# WiFire.net
KiCad netlist of a schematic drawn in EAGLE
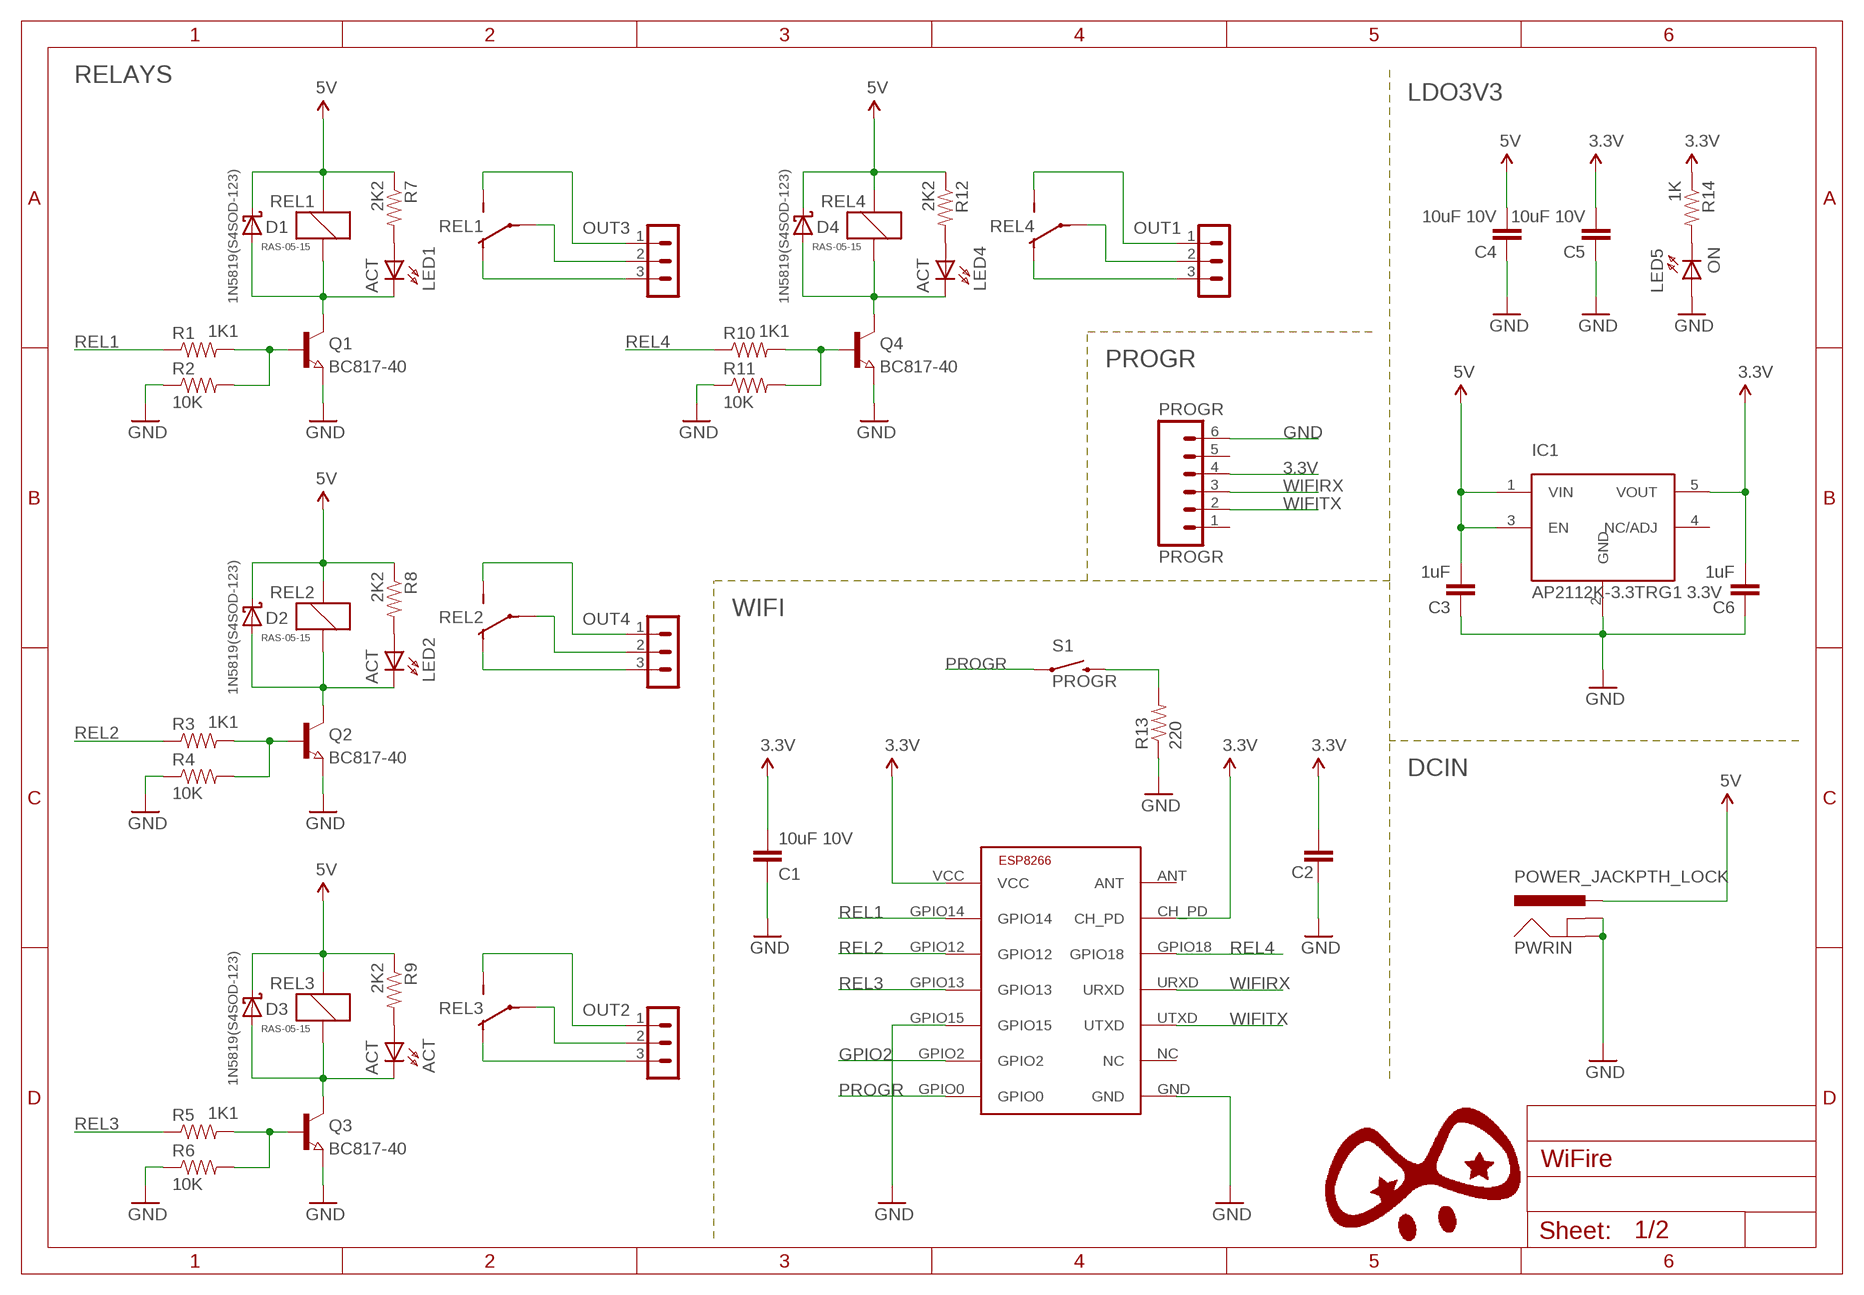
[diagram p0: schematic, sheet 1]
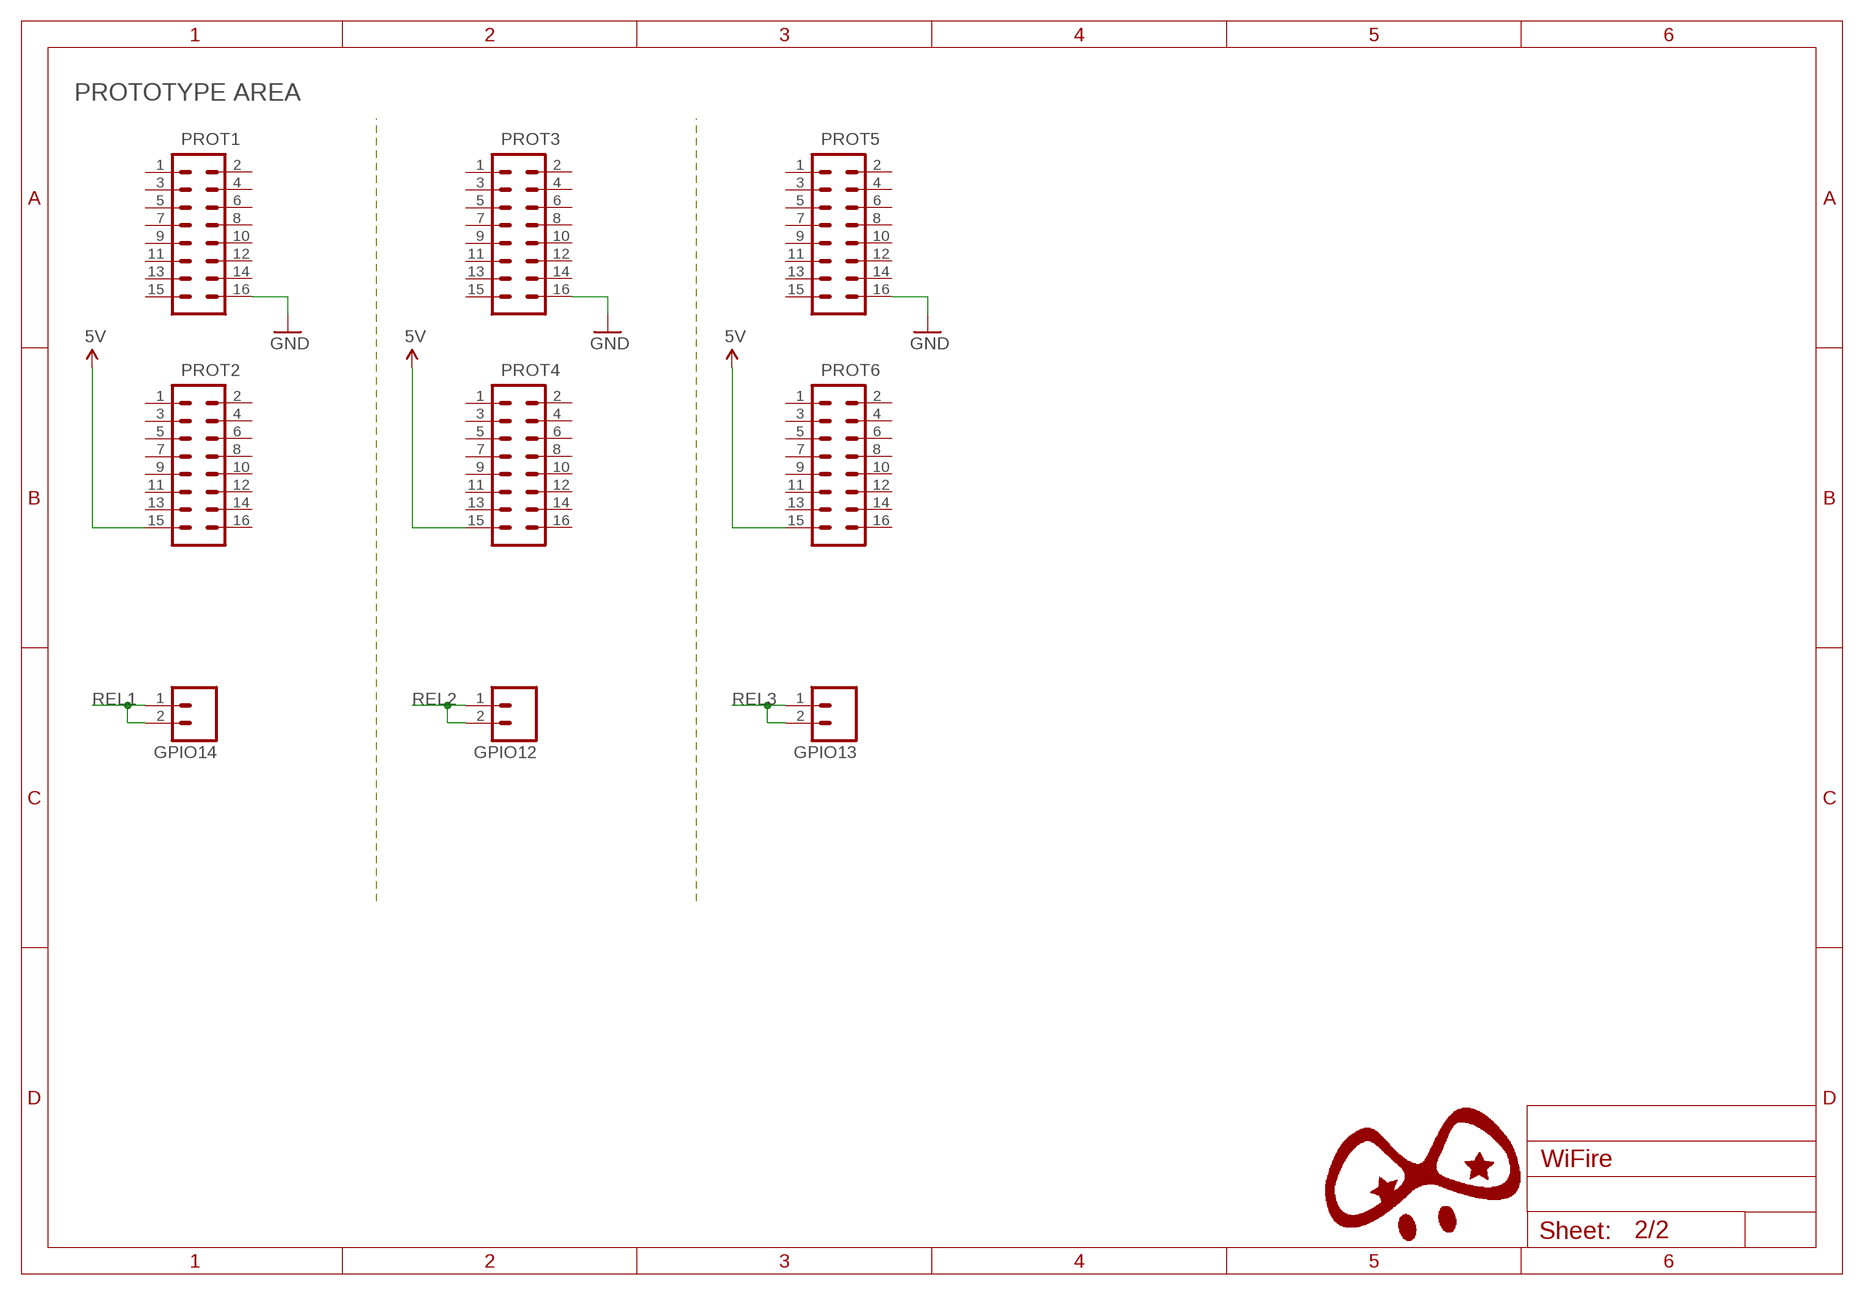
[diagram p1: schematic, sheet 2]

(export (version "E")
  (design (tool "Eeschema 10.0.6"))
  (components
    (comp (ref "ACT")
      (value "ACT")
      (footprint "eagle-import:LED-0603_L")
      (libsource (lib "eagle-import") (part "LED0603DWS_L"))
    )
    (comp (ref "C1")
      (value "10uF 10V")
      (footprint "eagle-import:0402-CAP")
      (libsource (lib "eagle-import") (part "CAP0402-CAP"))
    )
    (comp (ref "C2")
      (value "0.1uF")
      (footprint "eagle-import:0402-CAP")
      (libsource (lib "eagle-import") (part "CAP0402-CAP"))
    )
    (comp (ref "C3")
      (value "1uF")
      (footprint "eagle-import:0402-CAP")
      (libsource (lib "eagle-import") (part "CAP0402-CAP"))
    )
    (comp (ref "C4")
      (value "10uF 10V")
      (footprint "eagle-import:0402-CAP")
      (libsource (lib "eagle-import") (part "CAP0402-CAP"))
    )
    (comp (ref "C5")
      (value "10uF 10V")
      (footprint "eagle-import:0402-CAP")
      (libsource (lib "eagle-import") (part "CAP0402-CAP"))
    )
    (comp (ref "C6")
      (value "1uF")
      (footprint "eagle-import:0402-CAP")
      (libsource (lib "eagle-import") (part "CAP0402-CAP"))
    )
    (comp (ref "D1")
      (value "1N5819(S4SOD-123)")
      (footprint "eagle-import:SOD-123")
      (libsource (lib "eagle-import") (part "SCHOTKKY7.62SS-1N5819(S4SOD-123)"))
    )
    (comp (ref "D2")
      (value "1N5819(S4SOD-123)")
      (footprint "eagle-import:SOD-123")
      (libsource (lib "eagle-import") (part "SCHOTKKY7.62SS-1N5819(S4SOD-123)"))
    )
    (comp (ref "D3")
      (value "1N5819(S4SOD-123)")
      (footprint "eagle-import:SOD-123")
      (libsource (lib "eagle-import") (part "SCHOTKKY7.62SS-1N5819(S4SOD-123)"))
    )
    (comp (ref "D4")
      (value "1N5819(S4SOD-123)")
      (footprint "eagle-import:SOD-123")
      (libsource (lib "eagle-import") (part "SCHOTKKY7.62SS-1N5819(S4SOD-123)"))
    )
    (comp (ref "IC1")
      (value "AP2112K-3.3TRG1 3.3V")
      (footprint "eagle-import:SOT23-5")
      (libsource (lib "eagle-import") (part "5PIN_REG"))
    )
    (comp (ref "LED1")
      (value "ACT")
      (footprint "eagle-import:LED-0603_L")
      (libsource (lib "eagle-import") (part "LED0603DWS_L"))
    )
    (comp (ref "LED2")
      (value "ACT")
      (footprint "eagle-import:LED-0603_L")
      (libsource (lib "eagle-import") (part "LED0603DWS_L"))
    )
    (comp (ref "LED4")
      (value "ACT")
      (footprint "eagle-import:LED-0603_L")
      (libsource (lib "eagle-import") (part "LED0603DWS_L"))
    )
    (comp (ref "LED5")
      (value "ON")
      (footprint "eagle-import:LED-0603_L")
      (libsource (lib "eagle-import") (part "LED0603DWS_L"))
    )
    (comp (ref "OUT1")
      (value "CON3-DG306-5.0_3P(TB3-5MM)")
      (footprint "eagle-import:DG306-5.0_3P")
      (libsource (lib "eagle-import") (part "CON3-DG306-5.0_3P(TB3-5MM)"))
    )
    (comp (ref "OUT2")
      (value "CON3-DG306-5.0_3P(TB3-5MM)")
      (footprint "eagle-import:DG306-5.0_3P")
      (libsource (lib "eagle-import") (part "CON3-DG306-5.0_3P(TB3-5MM)"))
    )
    (comp (ref "OUT3")
      (value "CON3-DG306-5.0_3P(TB3-5MM)")
      (footprint "eagle-import:DG306-5.0_3P")
      (libsource (lib "eagle-import") (part "CON3-DG306-5.0_3P(TB3-5MM)"))
    )
    (comp (ref "OUT4")
      (value "CON3-DG306-5.0_3P(TB3-5MM)")
      (footprint "eagle-import:DG306-5.0_3P")
      (libsource (lib "eagle-import") (part "CON3-DG306-5.0_3P(TB3-5MM)"))
    )
    (comp (ref "PROGR")
      (value "PROGR")
      (footprint "eagle-import:1X06_SMD_MALE")
      (libsource (lib "eagle-import") (part "M06SMD_MALE"))
    )
    (comp (ref "PWRIN")
      (value "POWER_JACKPTH_LOCK")
      (footprint "eagle-import:POWER_JACK_PTH_LOCK")
      (libsource (lib "eagle-import") (part "POWER_JACKPTH_LOCK"))
    )
    (comp (ref "Q1")
      (value "BC817-40")
      (footprint "eagle-import:SOT23")
      (libsource (lib "eagle-import") (part "NPN-TRANSISTOR_SOT23"))
    )
    (comp (ref "Q2")
      (value "BC817-40")
      (footprint "eagle-import:SOT23")
      (libsource (lib "eagle-import") (part "NPN-TRANSISTOR_SOT23"))
    )
    (comp (ref "Q3")
      (value "BC817-40")
      (footprint "eagle-import:SOT23")
      (libsource (lib "eagle-import") (part "NPN-TRANSISTOR_SOT23"))
    )
    (comp (ref "Q4")
      (value "BC817-40")
      (footprint "eagle-import:SOT23")
      (libsource (lib "eagle-import") (part "NPN-TRANSISTOR_SOT23"))
    )
    (comp (ref "R1")
      (value "1K1")
      (footprint "eagle-import:0402-RES")
      (libsource (lib "eagle-import") (part "RESISTOR0402-RES"))
    )
    (comp (ref "R2")
      (value "10K")
      (footprint "eagle-import:0402-RES")
      (libsource (lib "eagle-import") (part "RESISTOR0402-RES"))
    )
    (comp (ref "R3")
      (value "1K1")
      (footprint "eagle-import:0402-RES")
      (libsource (lib "eagle-import") (part "RESISTOR0402-RES"))
    )
    (comp (ref "R4")
      (value "10K")
      (footprint "eagle-import:0402-RES")
      (libsource (lib "eagle-import") (part "RESISTOR0402-RES"))
    )
    (comp (ref "R5")
      (value "1K1")
      (footprint "eagle-import:0402-RES")
      (libsource (lib "eagle-import") (part "RESISTOR0402-RES"))
    )
    (comp (ref "R6")
      (value "10K")
      (footprint "eagle-import:0402-RES")
      (libsource (lib "eagle-import") (part "RESISTOR0402-RES"))
    )
    (comp (ref "R7")
      (value "2K2")
      (footprint "eagle-import:0402-RES")
      (libsource (lib "eagle-import") (part "RESISTOR0402-RES"))
    )
    (comp (ref "R8")
      (value "2K2")
      (footprint "eagle-import:0402-RES")
      (libsource (lib "eagle-import") (part "RESISTOR0402-RES"))
    )
    (comp (ref "R9")
      (value "2K2")
      (footprint "eagle-import:0402-RES")
      (libsource (lib "eagle-import") (part "RESISTOR0402-RES"))
    )
    (comp (ref "R10")
      (value "1K1")
      (footprint "eagle-import:0402-RES")
      (libsource (lib "eagle-import") (part "RESISTOR0402-RES"))
    )
    (comp (ref "R11")
      (value "10K")
      (footprint "eagle-import:0402-RES")
      (libsource (lib "eagle-import") (part "RESISTOR0402-RES"))
    )
    (comp (ref "R12")
      (value "2K2")
      (footprint "eagle-import:0402-RES")
      (libsource (lib "eagle-import") (part "RESISTOR0402-RES"))
    )
    (comp (ref "R13")
      (value "220")
      (footprint "eagle-import:0402-RES")
      (libsource (lib "eagle-import") (part "RESISTOR0402-RES"))
    )
    (comp (ref "R14")
      (value "1K")
      (footprint "eagle-import:0402-RES")
      (libsource (lib "eagle-import") (part "RESISTOR0402-RES"))
    )
    (comp (ref "REL1")
      (value "RAS-05-15")
      (footprint "eagle-import:H200-FAT")
      (libsource (lib "eagle-import") (part "RELAYH200F"))
    )
    (comp (ref "REL2")
      (value "RAS-05-15")
      (footprint "eagle-import:H200-FAT")
      (libsource (lib "eagle-import") (part "RELAYH200F"))
    )
    (comp (ref "REL3")
      (value "RAS-05-15")
      (footprint "eagle-import:H200-FAT")
      (libsource (lib "eagle-import") (part "RELAYH200F"))
    )
    (comp (ref "REL4")
      (value "RAS-05-15")
      (footprint "eagle-import:H200-FAT")
      (libsource (lib "eagle-import") (part "RELAYH200F"))
    )
    (comp (ref "S1")
      (value "PROGR")
      (footprint "eagle-import:TACTILE-PTH-SIDEEZ")
      (libsource (lib "eagle-import") (part "SWITCH-MOMENTARY-2SIDE_EZ"))
    )
    (comp (ref "U1")
      (value "ESP8266")
      (footprint "eagle-import:ESP-03")
      (libsource (lib "eagle-import") (part "ESP8266"))
    )
    (comp (ref "GPIO12")
      (value "M02PTH")
      (footprint "eagle-import:1X02")
      (libsource (lib "eagle-import") (part "M02PTH"))
    )
    (comp (ref "GPIO13")
      (value "M02PTH")
      (footprint "eagle-import:1X02")
      (libsource (lib "eagle-import") (part "M02PTH"))
    )
    (comp (ref "GPIO14")
      (value "M02PTH")
      (footprint "eagle-import:1X02")
      (libsource (lib "eagle-import") (part "M02PTH"))
    )
    (comp (ref "PROT1")
      (value "M08X2")
      (footprint "eagle-import:2X8")
      (libsource (lib "eagle-import") (part "M08X2"))
    )
    (comp (ref "PROT2")
      (value "M08X2")
      (footprint "eagle-import:2X8")
      (libsource (lib "eagle-import") (part "M08X2"))
    )
    (comp (ref "PROT3")
      (value "M08X2")
      (footprint "eagle-import:2X8")
      (libsource (lib "eagle-import") (part "M08X2"))
    )
    (comp (ref "PROT4")
      (value "M08X2")
      (footprint "eagle-import:2X8")
      (libsource (lib "eagle-import") (part "M08X2"))
    )
    (comp (ref "PROT5")
      (value "M08X2")
      (footprint "eagle-import:2X8")
      (libsource (lib "eagle-import") (part "M08X2"))
    )
    (comp (ref "PROT6")
      (value "M08X2")
      (footprint "eagle-import:2X8")
      (libsource (lib "eagle-import") (part "M08X2"))
    )
  )
  (nets
    (net (code "1") (name "3.3V") (class "Default")
      (node (ref "C1") (pin "2") (pinfunction "2_2") (pintype "passive"))
      (node (ref "C2") (pin "2") (pinfunction "2_2") (pintype "passive"))
      (node (ref "C5") (pin "2") (pinfunction "2_2") (pintype "passive"))
      (node (ref "C6") (pin "2") (pinfunction "2_2") (pintype "passive"))
      (node (ref "IC1") (pin "5") (pinfunction "VOUT_5") (pintype "bidirectional"))
      (node (ref "PROGR") (pin "4") (pinfunction "4_4") (pintype "passive"))
      (node (ref "R14") (pin "1") (pinfunction "1_1") (pintype "passive"))
      (node (ref "U1") (pin "CH_PD") (pinfunction "CH_PD_CH_PD") (pintype "bidirectional"))
      (node (ref "U1") (pin "VCC") (pinfunction "VCC_VCC") (pintype "bidirectional"))
    )
    (net (code "2") (name "5V") (class "Default")
      (node (ref "C3") (pin "2") (pinfunction "2_2") (pintype "passive"))
      (node (ref "C4") (pin "2") (pinfunction "2_2") (pintype "passive"))
      (node (ref "D1") (pin "C") (pinfunction "C_C") (pintype "passive"))
      (node (ref "D2") (pin "C") (pinfunction "C_C") (pintype "passive"))
      (node (ref "D3") (pin "C") (pinfunction "C_C") (pintype "passive"))
      (node (ref "D4") (pin "C") (pinfunction "C_C") (pintype "passive"))
      (node (ref "IC1") (pin "1") (pinfunction "VIN_1") (pintype "bidirectional"))
      (node (ref "IC1") (pin "3") (pinfunction "EN_3") (pintype "bidirectional"))
      (node (ref "PROT2") (pin "15") (pinfunction "15_15") (pintype "passive"))
      (node (ref "PROT4") (pin "15") (pinfunction "15_15") (pintype "passive"))
      (node (ref "PROT6") (pin "15") (pinfunction "15_15") (pintype "passive"))
      (node (ref "PWRIN") (pin "PWR") (pinfunction "PWR_PWR") (pintype "bidirectional"))
      (node (ref "R12") (pin "1") (pinfunction "1_1") (pintype "passive"))
      (node (ref "R7") (pin "1") (pinfunction "1_1") (pintype "passive"))
      (node (ref "R8") (pin "1") (pinfunction "1_1") (pintype "passive"))
      (node (ref "R9") (pin "1") (pinfunction "1_1") (pintype "passive"))
      (node (ref "REL1") (pin "1") (pinfunction "1_1") (pintype "passive"))
      (node (ref "REL2") (pin "1") (pinfunction "1_1") (pintype "passive"))
      (node (ref "REL3") (pin "1") (pinfunction "1_1") (pintype "passive"))
      (node (ref "REL4") (pin "1") (pinfunction "1_1") (pintype "passive"))
    )
    (net (code "3") (name "GND") (class "Default")
      (node (ref "C1") (pin "1") (pinfunction "1_1") (pintype "passive"))
      (node (ref "C2") (pin "1") (pinfunction "1_1") (pintype "passive"))
      (node (ref "C3") (pin "1") (pinfunction "1_1") (pintype "passive"))
      (node (ref "C4") (pin "1") (pinfunction "1_1") (pintype "passive"))
      (node (ref "C5") (pin "1") (pinfunction "1_1") (pintype "passive"))
      (node (ref "C6") (pin "1") (pinfunction "1_1") (pintype "passive"))
      (node (ref "IC1") (pin "2") (pinfunction "GND_2") (pintype "bidirectional"))
      (node (ref "LED5") (pin "A") (pinfunction "A_A") (pintype "passive"))
      (node (ref "PROGR") (pin "6") (pinfunction "6_6") (pintype "passive"))
      (node (ref "PROT1") (pin "16") (pinfunction "16_16") (pintype "passive"))
      (node (ref "PROT3") (pin "16") (pinfunction "16_16") (pintype "passive"))
      (node (ref "PROT5") (pin "16") (pinfunction "16_16") (pintype "passive"))
      (node (ref "PWRIN") (pin "GND") (pinfunction "GND_GND") (pintype "bidirectional"))
      (node (ref "PWRIN") (pin "GNDBREAK") (pinfunction "GNDBREAK_GNDBREAK") (pintype "bidirectional"))
      (node (ref "Q1") (pin "2") (pinfunction "E_2") (pintype "passive"))
      (node (ref "Q2") (pin "2") (pinfunction "E_2") (pintype "passive"))
      (node (ref "Q3") (pin "2") (pinfunction "E_2") (pintype "passive"))
      (node (ref "Q4") (pin "2") (pinfunction "E_2") (pintype "passive"))
      (node (ref "R11") (pin "1") (pinfunction "1_1") (pintype "passive"))
      (node (ref "R13") (pin "1") (pinfunction "1_1") (pintype "passive"))
      (node (ref "R2") (pin "1") (pinfunction "1_1") (pintype "passive"))
      (node (ref "R4") (pin "1") (pinfunction "1_1") (pintype "passive"))
      (node (ref "R6") (pin "1") (pinfunction "1_1") (pintype "passive"))
      (node (ref "U1") (pin "GND") (pinfunction "GND_GND") (pintype "bidirectional"))
      (node (ref "U1") (pin "GPIO15") (pinfunction "GPIO15_GPIO15") (pintype "bidirectional"))
    )
    (net (code "4") (name "GPIO2") (class "Default")
      (node (ref "U1") (pin "GPIO2") (pinfunction "GPIO2_GPIO2") (pintype "bidirectional"))
    )
    (net (code "5") (name "Net-(ACT-PadA)") (class "Default")
      (node (ref "ACT") (pin "A") (pinfunction "A_A") (pintype "passive"))
      (node (ref "R9") (pin "2") (pinfunction "2_2") (pintype "passive"))
    )
    (net (code "6") (name "Net-(LED1-PadA)") (class "Default")
      (node (ref "LED1") (pin "A") (pinfunction "A_A") (pintype "passive"))
      (node (ref "R7") (pin "2") (pinfunction "2_2") (pintype "passive"))
    )
    (net (code "7") (name "Net-(LED2-PadA)") (class "Default")
      (node (ref "LED2") (pin "A") (pinfunction "A_A") (pintype "passive"))
      (node (ref "R8") (pin "2") (pinfunction "2_2") (pintype "passive"))
    )
    (net (code "8") (name "Net-(LED4-PadA)") (class "Default")
      (node (ref "LED4") (pin "A") (pinfunction "A_A") (pintype "passive"))
      (node (ref "R12") (pin "2") (pinfunction "2_2") (pintype "passive"))
    )
    (net (code "9") (name "Net-(LED5-PadC)") (class "Default")
      (node (ref "LED5") (pin "C") (pinfunction "C_C") (pintype "passive"))
      (node (ref "R14") (pin "2") (pinfunction "2_2") (pintype "passive"))
    )
    (net (code "10") (name "Net-(OUT1-Pad1)") (class "Default")
      (node (ref "OUT1") (pin "1") (pinfunction "1_1") (pintype "passive"))
      (node (ref "REL4") (pin "S") (pinfunction "S_S") (pintype "passive"))
    )
    (net (code "11") (name "Net-(OUT1-Pad2)") (class "Default")
      (node (ref "OUT1") (pin "2") (pinfunction "2_2") (pintype "passive"))
      (node (ref "REL4") (pin "P") (pinfunction "P_P") (pintype "passive"))
    )
    (net (code "12") (name "Net-(OUT1-Pad3)") (class "Default")
      (node (ref "OUT1") (pin "3") (pinfunction "3_3") (pintype "passive"))
      (node (ref "REL4") (pin "O") (pinfunction "O_O") (pintype "passive"))
    )
    (net (code "13") (name "Net-(OUT2-Pad1)") (class "Default")
      (node (ref "OUT2") (pin "1") (pinfunction "1_1") (pintype "passive"))
      (node (ref "REL3") (pin "S") (pinfunction "S_S") (pintype "passive"))
    )
    (net (code "14") (name "Net-(OUT2-Pad2)") (class "Default")
      (node (ref "OUT2") (pin "2") (pinfunction "2_2") (pintype "passive"))
      (node (ref "REL3") (pin "P") (pinfunction "P_P") (pintype "passive"))
    )
    (net (code "15") (name "Net-(OUT2-Pad3)") (class "Default")
      (node (ref "OUT2") (pin "3") (pinfunction "3_3") (pintype "passive"))
      (node (ref "REL3") (pin "O") (pinfunction "O_O") (pintype "passive"))
    )
    (net (code "16") (name "Net-(OUT3-Pad1)") (class "Default")
      (node (ref "OUT3") (pin "1") (pinfunction "1_1") (pintype "passive"))
      (node (ref "REL1") (pin "S") (pinfunction "S_S") (pintype "passive"))
    )
    (net (code "17") (name "Net-(OUT3-Pad2)") (class "Default")
      (node (ref "OUT3") (pin "2") (pinfunction "2_2") (pintype "passive"))
      (node (ref "REL1") (pin "P") (pinfunction "P_P") (pintype "passive"))
    )
    (net (code "18") (name "Net-(OUT3-Pad3)") (class "Default")
      (node (ref "OUT3") (pin "3") (pinfunction "3_3") (pintype "passive"))
      (node (ref "REL1") (pin "O") (pinfunction "O_O") (pintype "passive"))
    )
    (net (code "19") (name "Net-(OUT4-Pad1)") (class "Default")
      (node (ref "OUT4") (pin "1") (pinfunction "1_1") (pintype "passive"))
      (node (ref "REL2") (pin "S") (pinfunction "S_S") (pintype "passive"))
    )
    (net (code "20") (name "Net-(OUT4-Pad2)") (class "Default")
      (node (ref "OUT4") (pin "2") (pinfunction "2_2") (pintype "passive"))
      (node (ref "REL2") (pin "P") (pinfunction "P_P") (pintype "passive"))
    )
    (net (code "21") (name "Net-(OUT4-Pad3)") (class "Default")
      (node (ref "OUT4") (pin "3") (pinfunction "3_3") (pintype "passive"))
      (node (ref "REL2") (pin "O") (pinfunction "O_O") (pintype "passive"))
    )
    (net (code "22") (name "Net-(Q1-B)") (class "Default")
      (node (ref "Q1") (pin "1") (pinfunction "B_1") (pintype "passive"))
      (node (ref "R1") (pin "2") (pinfunction "2_2") (pintype "passive"))
      (node (ref "R2") (pin "2") (pinfunction "2_2") (pintype "passive"))
    )
    (net (code "23") (name "Net-(Q1-C)") (class "Default")
      (node (ref "D1") (pin "A") (pinfunction "A_A") (pintype "passive"))
      (node (ref "LED1") (pin "C") (pinfunction "C_C") (pintype "passive"))
      (node (ref "Q1") (pin "3") (pinfunction "C_3") (pintype "passive"))
      (node (ref "REL1") (pin "2") (pinfunction "2_2") (pintype "passive"))
    )
    (net (code "24") (name "Net-(Q2-B)") (class "Default")
      (node (ref "Q2") (pin "1") (pinfunction "B_1") (pintype "passive"))
      (node (ref "R3") (pin "2") (pinfunction "2_2") (pintype "passive"))
      (node (ref "R4") (pin "2") (pinfunction "2_2") (pintype "passive"))
    )
    (net (code "25") (name "Net-(Q2-C)") (class "Default")
      (node (ref "D2") (pin "A") (pinfunction "A_A") (pintype "passive"))
      (node (ref "LED2") (pin "C") (pinfunction "C_C") (pintype "passive"))
      (node (ref "Q2") (pin "3") (pinfunction "C_3") (pintype "passive"))
      (node (ref "REL2") (pin "2") (pinfunction "2_2") (pintype "passive"))
    )
    (net (code "26") (name "Net-(Q3-B)") (class "Default")
      (node (ref "Q3") (pin "1") (pinfunction "B_1") (pintype "passive"))
      (node (ref "R5") (pin "2") (pinfunction "2_2") (pintype "passive"))
      (node (ref "R6") (pin "2") (pinfunction "2_2") (pintype "passive"))
    )
    (net (code "27") (name "Net-(Q3-C)") (class "Default")
      (node (ref "ACT") (pin "C") (pinfunction "C_C") (pintype "passive"))
      (node (ref "D3") (pin "A") (pinfunction "A_A") (pintype "passive"))
      (node (ref "Q3") (pin "3") (pinfunction "C_3") (pintype "passive"))
      (node (ref "REL3") (pin "2") (pinfunction "2_2") (pintype "passive"))
    )
    (net (code "28") (name "Net-(Q4-B)") (class "Default")
      (node (ref "Q4") (pin "1") (pinfunction "B_1") (pintype "passive"))
      (node (ref "R10") (pin "2") (pinfunction "2_2") (pintype "passive"))
      (node (ref "R11") (pin "2") (pinfunction "2_2") (pintype "passive"))
    )
    (net (code "29") (name "Net-(Q4-C)") (class "Default")
      (node (ref "D4") (pin "A") (pinfunction "A_A") (pintype "passive"))
      (node (ref "LED4") (pin "C") (pinfunction "C_C") (pintype "passive"))
      (node (ref "Q4") (pin "3") (pinfunction "C_3") (pintype "passive"))
      (node (ref "REL4") (pin "2") (pinfunction "2_2") (pintype "passive"))
    )
    (net (code "30") (name "Net-(R13-Pad2)") (class "Default")
      (node (ref "R13") (pin "2") (pinfunction "2_2") (pintype "passive"))
      (node (ref "S1") (pin "2") (pinfunction "2_2") (pintype "passive"))
    )
    (net (code "31") (name "PROGR") (class "Default")
      (node (ref "S1") (pin "1") (pinfunction "1_1") (pintype "passive"))
      (node (ref "U1") (pin "GPIO0") (pinfunction "GPIO0_GPIO0") (pintype "bidirectional"))
    )
    (net (code "32") (name "REL1") (class "Default")
      (node (ref "GPIO14") (pin "1") (pinfunction "1_1") (pintype "passive"))
      (node (ref "GPIO14") (pin "2") (pinfunction "2_2") (pintype "passive"))
      (node (ref "R1") (pin "1") (pinfunction "1_1") (pintype "passive"))
      (node (ref "U1") (pin "GPIO14") (pinfunction "GPIO14_GPIO14") (pintype "bidirectional"))
    )
    (net (code "33") (name "REL2") (class "Default")
      (node (ref "GPIO12") (pin "1") (pinfunction "1_1") (pintype "passive"))
      (node (ref "GPIO12") (pin "2") (pinfunction "2_2") (pintype "passive"))
      (node (ref "R3") (pin "1") (pinfunction "1_1") (pintype "passive"))
      (node (ref "U1") (pin "GPIO12") (pinfunction "GPIO12_GPIO12") (pintype "bidirectional"))
    )
    (net (code "34") (name "REL3") (class "Default")
      (node (ref "GPIO13") (pin "1") (pinfunction "1_1") (pintype "passive"))
      (node (ref "GPIO13") (pin "2") (pinfunction "2_2") (pintype "passive"))
      (node (ref "R5") (pin "1") (pinfunction "1_1") (pintype "passive"))
      (node (ref "U1") (pin "GPIO13") (pinfunction "GPIO13_GPIO13") (pintype "bidirectional"))
    )
    (net (code "35") (name "REL4") (class "Default")
      (node (ref "R10") (pin "1") (pinfunction "1_1") (pintype "passive"))
      (node (ref "U1") (pin "GPIO18") (pinfunction "GPIO18_GPIO18") (pintype "bidirectional"))
    )
    (net (code "36") (name "WIFIRX") (class "Default")
      (node (ref "PROGR") (pin "3") (pinfunction "3_3") (pintype "passive"))
      (node (ref "U1") (pin "URXD") (pinfunction "URXD_URXD") (pintype "bidirectional"))
    )
    (net (code "37") (name "WIFITX") (class "Default")
      (node (ref "PROGR") (pin "2") (pinfunction "2_2") (pintype "passive"))
      (node (ref "U1") (pin "UTXD") (pinfunction "UTXD_UTXD") (pintype "bidirectional"))
    )
    (net (code "38") (name "unconnected-(IC1-NC{slash}ADJ-Pad4)") (class "Default")
      (node (ref "IC1") (pin "4") (pinfunction "NC/ADJ_4") (pintype "bidirectional"))
    )
    (net (code "39") (name "unconnected-(PROGR-Pad1)") (class "Default")
      (node (ref "PROGR") (pin "1") (pinfunction "1_1") (pintype "passive"))
    )
    (net (code "40") (name "unconnected-(PROGR-Pad5)") (class "Default")
      (node (ref "PROGR") (pin "5") (pinfunction "5_5") (pintype "passive"))
    )
    (net (code "41") (name "unconnected-(PROT1-Pad1)") (class "Default")
      (node (ref "PROT1") (pin "1") (pinfunction "1_1") (pintype "passive"))
    )
    (net (code "42") (name "unconnected-(PROT1-Pad2)") (class "Default")
      (node (ref "PROT1") (pin "2") (pinfunction "2_2") (pintype "passive"))
    )
    (net (code "43") (name "unconnected-(PROT1-Pad3)") (class "Default")
      (node (ref "PROT1") (pin "3") (pinfunction "3_3") (pintype "passive"))
    )
    (net (code "44") (name "unconnected-(PROT1-Pad4)") (class "Default")
      (node (ref "PROT1") (pin "4") (pinfunction "4_4") (pintype "passive"))
    )
    (net (code "45") (name "unconnected-(PROT1-Pad5)") (class "Default")
      (node (ref "PROT1") (pin "5") (pinfunction "5_5") (pintype "passive"))
    )
    (net (code "46") (name "unconnected-(PROT1-Pad6)") (class "Default")
      (node (ref "PROT1") (pin "6") (pinfunction "6_6") (pintype "passive"))
    )
    (net (code "47") (name "unconnected-(PROT1-Pad7)") (class "Default")
      (node (ref "PROT1") (pin "7") (pinfunction "7_7") (pintype "passive"))
    )
    (net (code "48") (name "unconnected-(PROT1-Pad8)") (class "Default")
      (node (ref "PROT1") (pin "8") (pinfunction "8_8") (pintype "passive"))
    )
    (net (code "49") (name "unconnected-(PROT1-Pad9)") (class "Default")
      (node (ref "PROT1") (pin "9") (pinfunction "9_9") (pintype "passive"))
    )
    (net (code "50") (name "unconnected-(PROT1-Pad10)") (class "Default")
      (node (ref "PROT1") (pin "10") (pinfunction "10_10") (pintype "passive"))
    )
    (net (code "51") (name "unconnected-(PROT1-Pad11)") (class "Default")
      (node (ref "PROT1") (pin "11") (pinfunction "11_11") (pintype "passive"))
    )
    (net (code "52") (name "unconnected-(PROT1-Pad12)") (class "Default")
      (node (ref "PROT1") (pin "12") (pinfunction "12_12") (pintype "passive"))
    )
    (net (code "53") (name "unconnected-(PROT1-Pad13)") (class "Default")
      (node (ref "PROT1") (pin "13") (pinfunction "13_13") (pintype "passive"))
    )
    (net (code "54") (name "unconnected-(PROT1-Pad14)") (class "Default")
      (node (ref "PROT1") (pin "14") (pinfunction "14_14") (pintype "passive"))
    )
    (net (code "55") (name "unconnected-(PROT1-Pad15)") (class "Default")
      (node (ref "PROT1") (pin "15") (pinfunction "15_15") (pintype "passive"))
    )
    (net (code "56") (name "unconnected-(PROT2-Pad1)") (class "Default")
      (node (ref "PROT2") (pin "1") (pinfunction "1_1") (pintype "passive"))
    )
    (net (code "57") (name "unconnected-(PROT2-Pad2)") (class "Default")
      (node (ref "PROT2") (pin "2") (pinfunction "2_2") (pintype "passive"))
    )
    (net (code "58") (name "unconnected-(PROT2-Pad3)") (class "Default")
      (node (ref "PROT2") (pin "3") (pinfunction "3_3") (pintype "passive"))
    )
    (net (code "59") (name "unconnected-(PROT2-Pad4)") (class "Default")
      (node (ref "PROT2") (pin "4") (pinfunction "4_4") (pintype "passive"))
    )
    (net (code "60") (name "unconnected-(PROT2-Pad5)") (class "Default")
      (node (ref "PROT2") (pin "5") (pinfunction "5_5") (pintype "passive"))
    )
    (net (code "61") (name "unconnected-(PROT2-Pad6)") (class "Default")
      (node (ref "PROT2") (pin "6") (pinfunction "6_6") (pintype "passive"))
    )
    (net (code "62") (name "unconnected-(PROT2-Pad7)") (class "Default")
      (node (ref "PROT2") (pin "7") (pinfunction "7_7") (pintype "passive"))
    )
    (net (code "63") (name "unconnected-(PROT2-Pad8)") (class "Default")
      (node (ref "PROT2") (pin "8") (pinfunction "8_8") (pintype "passive"))
    )
    (net (code "64") (name "unconnected-(PROT2-Pad9)") (class "Default")
      (node (ref "PROT2") (pin "9") (pinfunction "9_9") (pintype "passive"))
    )
    (net (code "65") (name "unconnected-(PROT2-Pad10)") (class "Default")
      (node (ref "PROT2") (pin "10") (pinfunction "10_10") (pintype "passive"))
    )
    (net (code "66") (name "unconnected-(PROT2-Pad11)") (class "Default")
      (node (ref "PROT2") (pin "11") (pinfunction "11_11") (pintype "passive"))
    )
    (net (code "67") (name "unconnected-(PROT2-Pad12)") (class "Default")
      (node (ref "PROT2") (pin "12") (pinfunction "12_12") (pintype "passive"))
    )
    (net (code "68") (name "unconnected-(PROT2-Pad13)") (class "Default")
      (node (ref "PROT2") (pin "13") (pinfunction "13_13") (pintype "passive"))
    )
    (net (code "69") (name "unconnected-(PROT2-Pad14)") (class "Default")
      (node (ref "PROT2") (pin "14") (pinfunction "14_14") (pintype "passive"))
    )
    (net (code "70") (name "unconnected-(PROT2-Pad16)") (class "Default")
      (node (ref "PROT2") (pin "16") (pinfunction "16_16") (pintype "passive"))
    )
    (net (code "71") (name "unconnected-(PROT3-Pad1)") (class "Default")
      (node (ref "PROT3") (pin "1") (pinfunction "1_1") (pintype "passive"))
    )
    (net (code "72") (name "unconnected-(PROT3-Pad2)") (class "Default")
      (node (ref "PROT3") (pin "2") (pinfunction "2_2") (pintype "passive"))
    )
    (net (code "73") (name "unconnected-(PROT3-Pad3)") (class "Default")
      (node (ref "PROT3") (pin "3") (pinfunction "3_3") (pintype "passive"))
    )
    (net (code "74") (name "unconnected-(PROT3-Pad4)") (class "Default")
      (node (ref "PROT3") (pin "4") (pinfunction "4_4") (pintype "passive"))
    )
    (net (code "75") (name "unconnected-(PROT3-Pad5)") (class "Default")
      (node (ref "PROT3") (pin "5") (pinfunction "5_5") (pintype "passive"))
    )
    (net (code "76") (name "unconnected-(PROT3-Pad6)") (class "Default")
      (node (ref "PROT3") (pin "6") (pinfunction "6_6") (pintype "passive"))
    )
    (net (code "77") (name "unconnected-(PROT3-Pad7)") (class "Default")
      (node (ref "PROT3") (pin "7") (pinfunction "7_7") (pintype "passive"))
    )
    (net (code "78") (name "unconnected-(PROT3-Pad8)") (class "Default")
      (node (ref "PROT3") (pin "8") (pinfunction "8_8") (pintype "passive"))
    )
    (net (code "79") (name "unconnected-(PROT3-Pad9)") (class "Default")
      (node (ref "PROT3") (pin "9") (pinfunction "9_9") (pintype "passive"))
    )
    (net (code "80") (name "unconnected-(PROT3-Pad10)") (class "Default")
      (node (ref "PROT3") (pin "10") (pinfunction "10_10") (pintype "passive"))
    )
    (net (code "81") (name "unconnected-(PROT3-Pad11)") (class "Default")
      (node (ref "PROT3") (pin "11") (pinfunction "11_11") (pintype "passive"))
    )
    (net (code "82") (name "unconnected-(PROT3-Pad12)") (class "Default")
      (node (ref "PROT3") (pin "12") (pinfunction "12_12") (pintype "passive"))
    )
    (net (code "83") (name "unconnected-(PROT3-Pad13)") (class "Default")
      (node (ref "PROT3") (pin "13") (pinfunction "13_13") (pintype "passive"))
    )
    (net (code "84") (name "unconnected-(PROT3-Pad14)") (class "Default")
      (node (ref "PROT3") (pin "14") (pinfunction "14_14") (pintype "passive"))
    )
    (net (code "85") (name "unconnected-(PROT3-Pad15)") (class "Default")
      (node (ref "PROT3") (pin "15") (pinfunction "15_15") (pintype "passive"))
    )
    (net (code "86") (name "unconnected-(PROT4-Pad1)") (class "Default")
      (node (ref "PROT4") (pin "1") (pinfunction "1_1") (pintype "passive"))
    )
    (net (code "87") (name "unconnected-(PROT4-Pad2)") (class "Default")
      (node (ref "PROT4") (pin "2") (pinfunction "2_2") (pintype "passive"))
    )
    (net (code "88") (name "unconnected-(PROT4-Pad3)") (class "Default")
      (node (ref "PROT4") (pin "3") (pinfunction "3_3") (pintype "passive"))
    )
    (net (code "89") (name "unconnected-(PROT4-Pad4)") (class "Default")
      (node (ref "PROT4") (pin "4") (pinfunction "4_4") (pintype "passive"))
    )
    (net (code "90") (name "unconnected-(PROT4-Pad5)") (class "Default")
      (node (ref "PROT4") (pin "5") (pinfunction "5_5") (pintype "passive"))
    )
    (net (code "91") (name "unconnected-(PROT4-Pad6)") (class "Default")
      (node (ref "PROT4") (pin "6") (pinfunction "6_6") (pintype "passive"))
    )
    (net (code "92") (name "unconnected-(PROT4-Pad7)") (class "Default")
      (node (ref "PROT4") (pin "7") (pinfunction "7_7") (pintype "passive"))
    )
    (net (code "93") (name "unconnected-(PROT4-Pad8)") (class "Default")
      (node (ref "PROT4") (pin "8") (pinfunction "8_8") (pintype "passive"))
    )
    (net (code "94") (name "unconnected-(PROT4-Pad9)") (class "Default")
      (node (ref "PROT4") (pin "9") (pinfunction "9_9") (pintype "passive"))
    )
    (net (code "95") (name "unconnected-(PROT4-Pad10)") (class "Default")
      (node (ref "PROT4") (pin "10") (pinfunction "10_10") (pintype "passive"))
    )
    (net (code "96") (name "unconnected-(PROT4-Pad11)") (class "Default")
      (node (ref "PROT4") (pin "11") (pinfunction "11_11") (pintype "passive"))
    )
    (net (code "97") (name "unconnected-(PROT4-Pad12)") (class "Default")
      (node (ref "PROT4") (pin "12") (pinfunction "12_12") (pintype "passive"))
    )
    (net (code "98") (name "unconnected-(PROT4-Pad13)") (class "Default")
      (node (ref "PROT4") (pin "13") (pinfunction "13_13") (pintype "passive"))
    )
    (net (code "99") (name "unconnected-(PROT4-Pad14)") (class "Default")
      (node (ref "PROT4") (pin "14") (pinfunction "14_14") (pintype "passive"))
    )
    (net (code "100") (name "unconnected-(PROT4-Pad16)") (class "Default")
      (node (ref "PROT4") (pin "16") (pinfunction "16_16") (pintype "passive"))
    )
    (net (code "101") (name "unconnected-(PROT5-Pad1)") (class "Default")
      (node (ref "PROT5") (pin "1") (pinfunction "1_1") (pintype "passive"))
    )
    (net (code "102") (name "unconnected-(PROT5-Pad2)") (class "Default")
      (node (ref "PROT5") (pin "2") (pinfunction "2_2") (pintype "passive"))
    )
    (net (code "103") (name "unconnected-(PROT5-Pad3)") (class "Default")
      (node (ref "PROT5") (pin "3") (pinfunction "3_3") (pintype "passive"))
    )
    (net (code "104") (name "unconnected-(PROT5-Pad4)") (class "Default")
      (node (ref "PROT5") (pin "4") (pinfunction "4_4") (pintype "passive"))
    )
    (net (code "105") (name "unconnected-(PROT5-Pad5)") (class "Default")
      (node (ref "PROT5") (pin "5") (pinfunction "5_5") (pintype "passive"))
    )
    (net (code "106") (name "unconnected-(PROT5-Pad6)") (class "Default")
      (node (ref "PROT5") (pin "6") (pinfunction "6_6") (pintype "passive"))
    )
    (net (code "107") (name "unconnected-(PROT5-Pad7)") (class "Default")
      (node (ref "PROT5") (pin "7") (pinfunction "7_7") (pintype "passive"))
    )
    (net (code "108") (name "unconnected-(PROT5-Pad8)") (class "Default")
      (node (ref "PROT5") (pin "8") (pinfunction "8_8") (pintype "passive"))
    )
    (net (code "109") (name "unconnected-(PROT5-Pad9)") (class "Default")
      (node (ref "PROT5") (pin "9") (pinfunction "9_9") (pintype "passive"))
    )
    (net (code "110") (name "unconnected-(PROT5-Pad10)") (class "Default")
      (node (ref "PROT5") (pin "10") (pinfunction "10_10") (pintype "passive"))
    )
    (net (code "111") (name "unconnected-(PROT5-Pad11)") (class "Default")
      (node (ref "PROT5") (pin "11") (pinfunction "11_11") (pintype "passive"))
    )
    (net (code "112") (name "unconnected-(PROT5-Pad12)") (class "Default")
      (node (ref "PROT5") (pin "12") (pinfunction "12_12") (pintype "passive"))
    )
    (net (code "113") (name "unconnected-(PROT5-Pad13)") (class "Default")
      (node (ref "PROT5") (pin "13") (pinfunction "13_13") (pintype "passive"))
    )
    (net (code "114") (name "unconnected-(PROT5-Pad14)") (class "Default")
      (node (ref "PROT5") (pin "14") (pinfunction "14_14") (pintype "passive"))
    )
    (net (code "115") (name "unconnected-(PROT5-Pad15)") (class "Default")
      (node (ref "PROT5") (pin "15") (pinfunction "15_15") (pintype "passive"))
    )
    (net (code "116") (name "unconnected-(PROT6-Pad1)") (class "Default")
      (node (ref "PROT6") (pin "1") (pinfunction "1_1") (pintype "passive"))
    )
    (net (code "117") (name "unconnected-(PROT6-Pad2)") (class "Default")
      (node (ref "PROT6") (pin "2") (pinfunction "2_2") (pintype "passive"))
    )
    (net (code "118") (name "unconnected-(PROT6-Pad3)") (class "Default")
      (node (ref "PROT6") (pin "3") (pinfunction "3_3") (pintype "passive"))
    )
    (net (code "119") (name "unconnected-(PROT6-Pad4)") (class "Default")
      (node (ref "PROT6") (pin "4") (pinfunction "4_4") (pintype "passive"))
    )
    (net (code "120") (name "unconnected-(PROT6-Pad5)") (class "Default")
      (node (ref "PROT6") (pin "5") (pinfunction "5_5") (pintype "passive"))
    )
    (net (code "121") (name "unconnected-(PROT6-Pad6)") (class "Default")
      (node (ref "PROT6") (pin "6") (pinfunction "6_6") (pintype "passive"))
    )
    (net (code "122") (name "unconnected-(PROT6-Pad7)") (class "Default")
      (node (ref "PROT6") (pin "7") (pinfunction "7_7") (pintype "passive"))
    )
    (net (code "123") (name "unconnected-(PROT6-Pad8)") (class "Default")
      (node (ref "PROT6") (pin "8") (pinfunction "8_8") (pintype "passive"))
    )
    (net (code "124") (name "unconnected-(PROT6-Pad9)") (class "Default")
      (node (ref "PROT6") (pin "9") (pinfunction "9_9") (pintype "passive"))
    )
    (net (code "125") (name "unconnected-(PROT6-Pad10)") (class "Default")
      (node (ref "PROT6") (pin "10") (pinfunction "10_10") (pintype "passive"))
    )
    (net (code "126") (name "unconnected-(PROT6-Pad11)") (class "Default")
      (node (ref "PROT6") (pin "11") (pinfunction "11_11") (pintype "passive"))
    )
    (net (code "127") (name "unconnected-(PROT6-Pad12)") (class "Default")
      (node (ref "PROT6") (pin "12") (pinfunction "12_12") (pintype "passive"))
    )
    (net (code "128") (name "unconnected-(PROT6-Pad13)") (class "Default")
      (node (ref "PROT6") (pin "13") (pinfunction "13_13") (pintype "passive"))
    )
    (net (code "129") (name "unconnected-(PROT6-Pad14)") (class "Default")
      (node (ref "PROT6") (pin "14") (pinfunction "14_14") (pintype "passive"))
    )
    (net (code "130") (name "unconnected-(PROT6-Pad16)") (class "Default")
      (node (ref "PROT6") (pin "16") (pinfunction "16_16") (pintype "passive"))
    )
    (net (code "131") (name "unconnected-(U1-PadANT)") (class "Default")
      (node (ref "U1") (pin "ANT") (pinfunction "ANT_ANT") (pintype "bidirectional"))
    )
    (net (code "132") (name "unconnected-(U1-PadNC)") (class "Default")
      (node (ref "U1") (pin "NC") (pinfunction "NC_NC") (pintype "bidirectional"))
    )
  )
)
